# ProProject_Tautek_nRF5340_2024-01-15.net
KiCad netlist of a schematic drawn in EasyEDA Pro
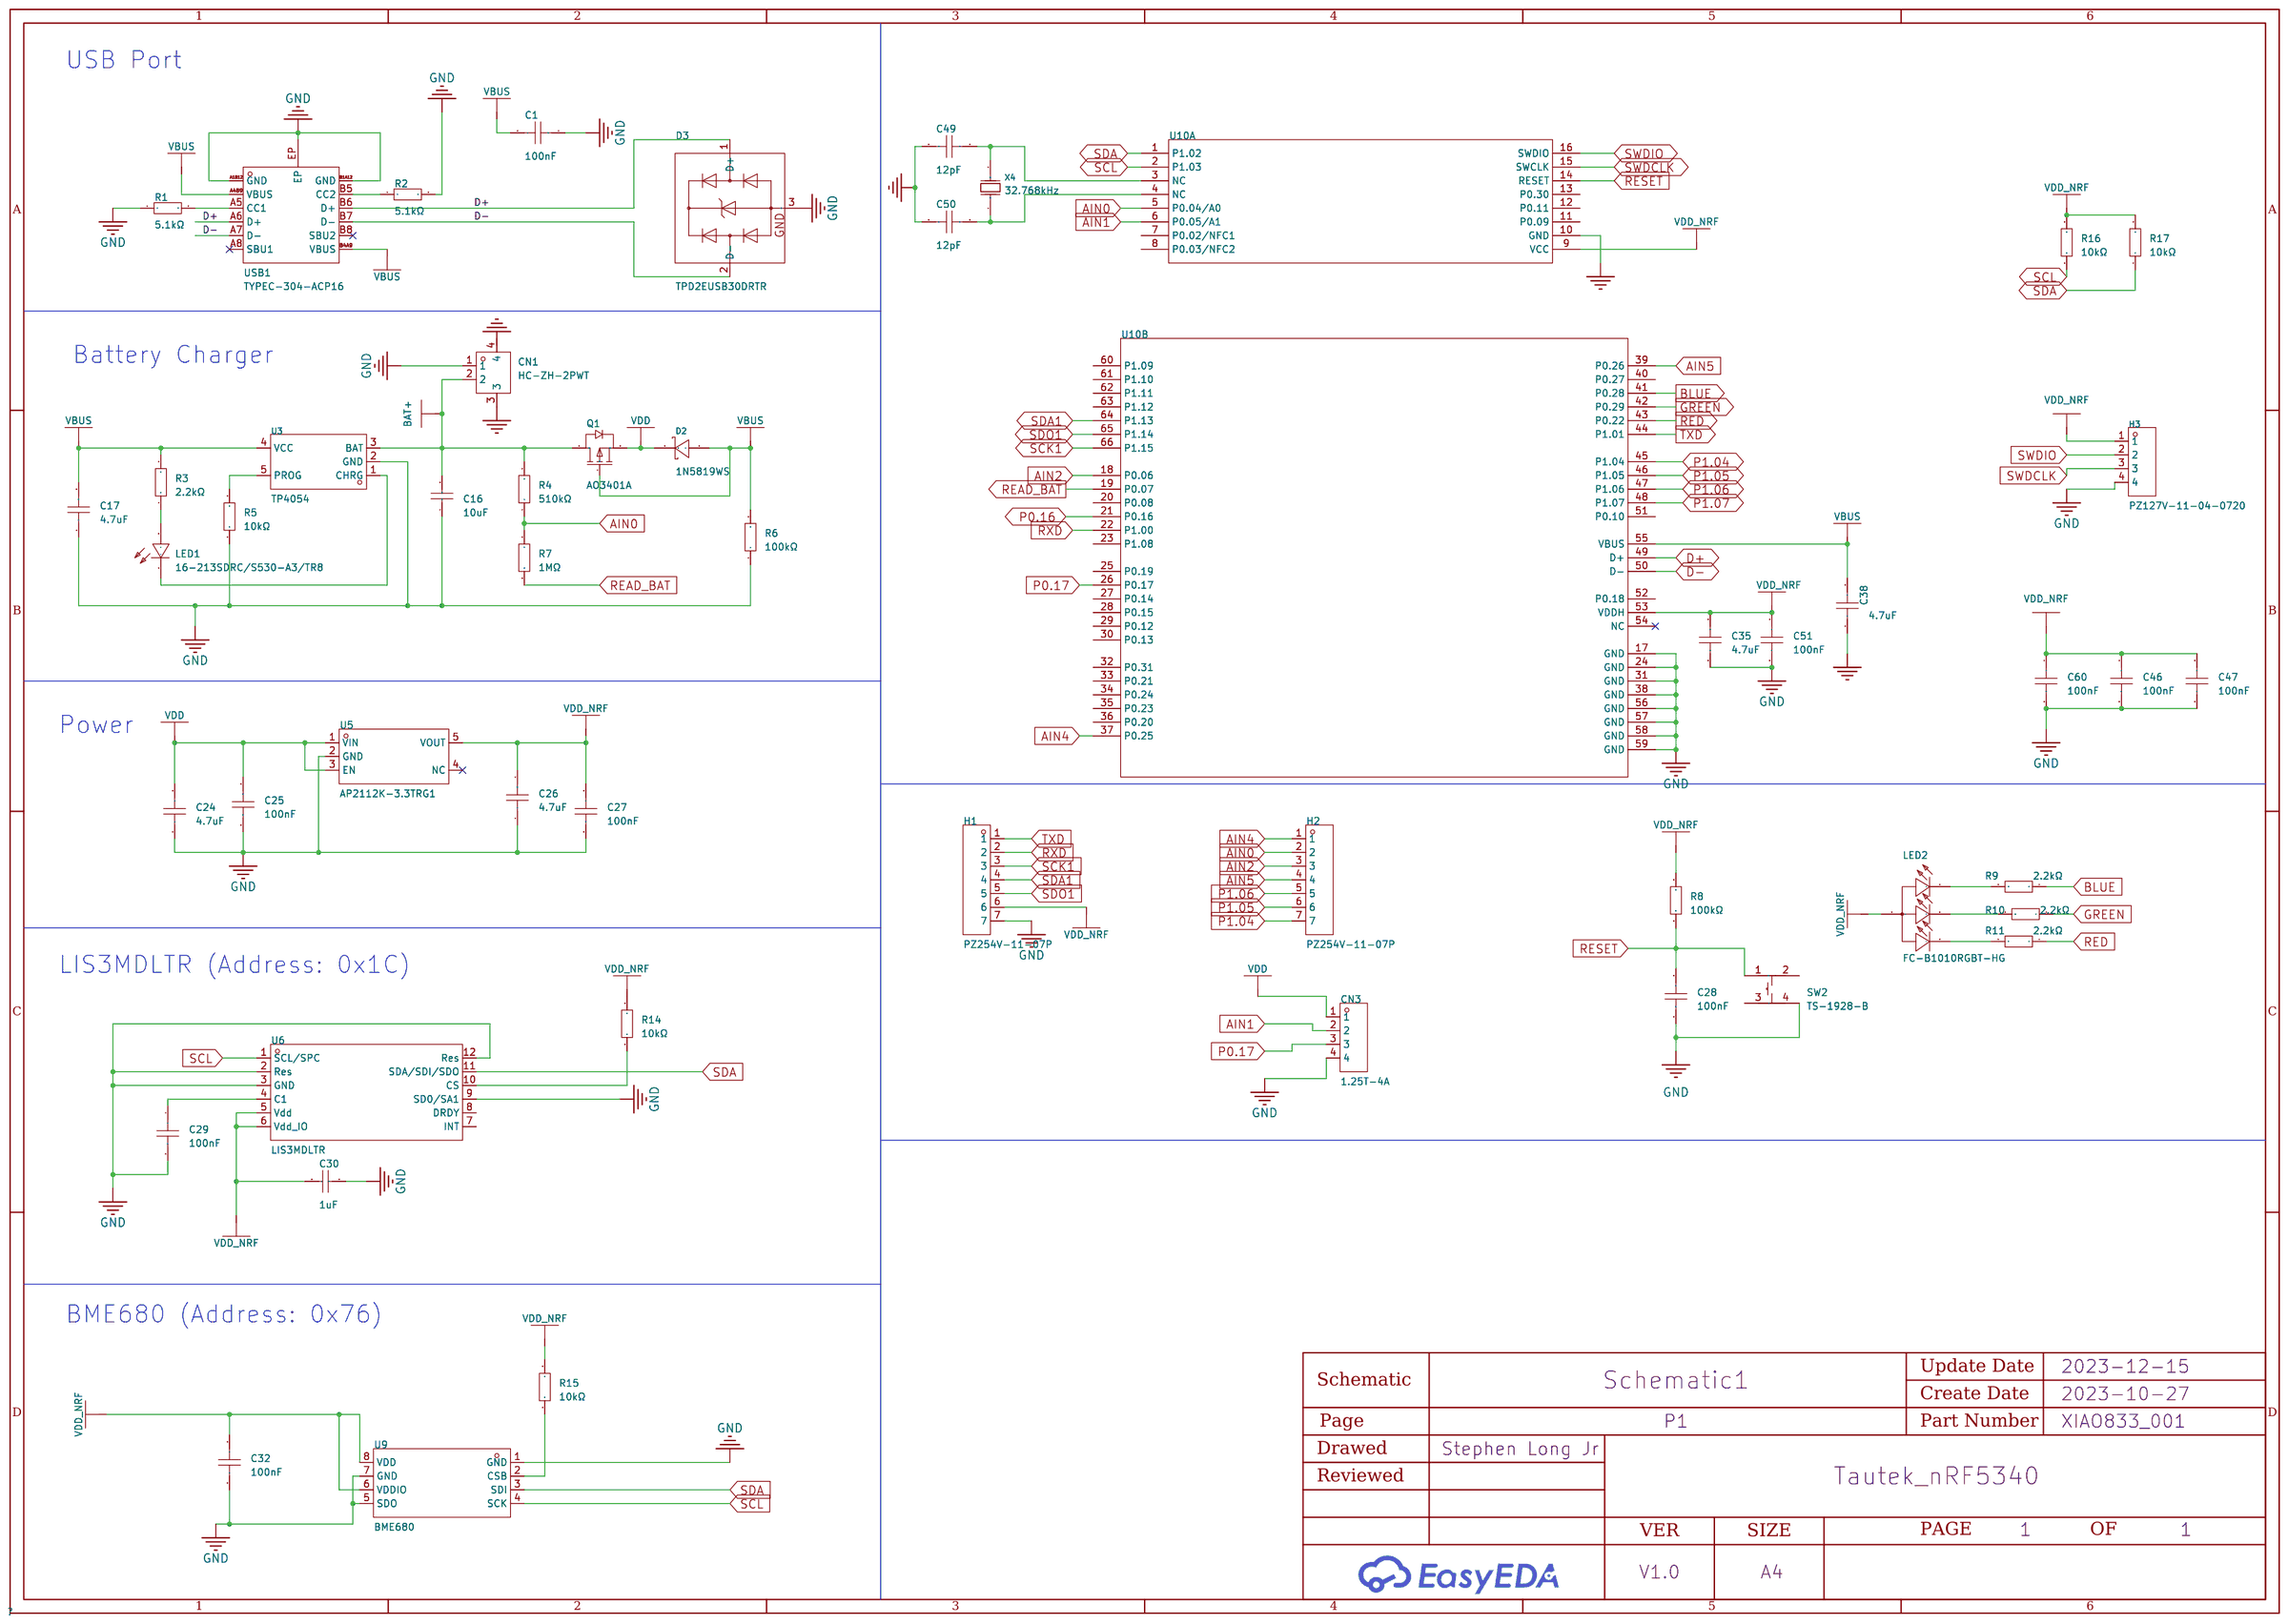
[diagram p0: schematic sheet]

(export (version "E")
  (design (tool "Eeschema 10.0.6"))
  (components
    (comp (ref "C1")
      (value "100nF")
      (footprint "easyedapro:C0201")
      (fields
        (field (name "Manufacturer Part") "CL03A104KQ3NNNC")
        (field (name "Manufacturer") "SAMSUNG(三星)")
      )
      (libsource (lib "easyedapro") (part "CL03A104KQ3NNNC"))
    )
    (comp (ref "C16")
      (value "10uF")
      (footprint "easyedapro:C0402")
      (fields
        (field (name "Manufacturer Part") "CL05A106MQ5NUNC")
        (field (name "Manufacturer") "SAMSUNG(三星)")
      )
      (libsource (lib "easyedapro") (part "CL05A106MQ5NUNC"))
    )
    (comp (ref "C17")
      (value "4.7uF")
      (footprint "easyedapro:C0201")
      (fields
        (field (name "Manufacturer Part") "GRM035R60J475ME15D")
        (field (name "Manufacturer") "muRata(村田)")
      )
      (libsource (lib "easyedapro") (part "GRM035R60J475ME15D"))
    )
    (comp (ref "C24")
      (value "4.7uF")
      (footprint "easyedapro:C0201")
      (fields
        (field (name "Manufacturer Part") "GRM035R60J475ME15D")
        (field (name "Manufacturer") "muRata(村田)")
      )
      (libsource (lib "easyedapro") (part "GRM035R60J475ME15D"))
    )
    (comp (ref "C25")
      (value "100nF")
      (footprint "easyedapro:C0201")
      (fields
        (field (name "Manufacturer Part") "CL03A104KQ3NNNC")
        (field (name "Manufacturer") "SAMSUNG(三星)")
      )
      (libsource (lib "easyedapro") (part "CL03A104KQ3NNNC"))
    )
    (comp (ref "C26")
      (value "4.7uF")
      (footprint "easyedapro:C0201")
      (fields
        (field (name "Manufacturer Part") "GRM035R60J475ME15D")
        (field (name "Manufacturer") "muRata(村田)")
      )
      (libsource (lib "easyedapro") (part "GRM035R60J475ME15D"))
    )
    (comp (ref "C27")
      (value "100nF")
      (footprint "easyedapro:C0201")
      (fields
        (field (name "Manufacturer Part") "CL03A104KQ3NNNC")
        (field (name "Manufacturer") "SAMSUNG(三星)")
      )
      (libsource (lib "easyedapro") (part "CL03A104KQ3NNNC"))
    )
    (comp (ref "C28")
      (value "100nF")
      (footprint "easyedapro:C0201")
      (fields
        (field (name "Manufacturer Part") "CL03A104KQ3NNNC")
        (field (name "Manufacturer") "SAMSUNG(三星)")
      )
      (libsource (lib "easyedapro") (part "CL03A104KQ3NNNC"))
    )
    (comp (ref "C29")
      (value "100nF")
      (footprint "easyedapro:C0201")
      (fields
        (field (name "Manufacturer Part") "CL03A104KQ3NNNC")
        (field (name "Manufacturer") "SAMSUNG(三星)")
      )
      (libsource (lib "easyedapro") (part "CL03A104KQ3NNNC"))
    )
    (comp (ref "C30")
      (value "1uF")
      (footprint "easyedapro:C0201")
      (fields
        (field (name "Manufacturer Part") "GRM033R60J105KEA2D")
        (field (name "Manufacturer") "muRata(村田)")
      )
      (libsource (lib "easyedapro") (part "GRM033R60J105KEA2D"))
    )
    (comp (ref "C32")
      (value "100nF")
      (footprint "easyedapro:C0201")
      (fields
        (field (name "Manufacturer Part") "CL03A104KQ3NNNC")
        (field (name "Manufacturer") "SAMSUNG(三星)")
      )
      (libsource (lib "easyedapro") (part "CL03A104KQ3NNNC"))
    )
    (comp (ref "C35")
      (value "4.7uF")
      (footprint "easyedapro:C0201")
      (fields
        (field (name "Manufacturer Part") "GRM035R60J475ME15D")
        (field (name "Manufacturer") "muRata(村田)")
      )
      (libsource (lib "easyedapro") (part "GRM035R60J475ME15D"))
    )
    (comp (ref "C38")
      (value "4.7uF")
      (footprint "easyedapro:C0201")
      (fields
        (field (name "Manufacturer Part") "GRM035R60J475ME15D")
        (field (name "Manufacturer") "muRata(村田)")
      )
      (libsource (lib "easyedapro") (part "GRM035R60J475ME15D"))
    )
    (comp (ref "C46")
      (value "100nF")
      (footprint "easyedapro:C0201")
      (fields
        (field (name "Manufacturer Part") "CL03A104KQ3NNNC")
        (field (name "Manufacturer") "SAMSUNG(三星)")
      )
      (libsource (lib "easyedapro") (part "CL03A104KQ3NNNC"))
    )
    (comp (ref "C47")
      (value "100nF")
      (footprint "easyedapro:C0201")
      (fields
        (field (name "Manufacturer Part") "CL03A104KQ3NNNC")
        (field (name "Manufacturer") "SAMSUNG(三星)")
      )
      (libsource (lib "easyedapro") (part "CL03A104KQ3NNNC"))
    )
    (comp (ref "C49")
      (value "12pF")
      (footprint "easyedapro:C0201")
      (fields
        (field (name "Manufacturer Part") "GRM0335C1H120FA01D")
        (field (name "Manufacturer") "muRata(村田)")
      )
      (libsource (lib "easyedapro") (part "GRM0335C1H120FA01D"))
    )
    (comp (ref "C50")
      (value "12pF")
      (footprint "easyedapro:C0201")
      (fields
        (field (name "Manufacturer Part") "GRM0335C1H120FA01D")
        (field (name "Manufacturer") "muRata(村田)")
      )
      (libsource (lib "easyedapro") (part "GRM0335C1H120FA01D"))
    )
    (comp (ref "C51")
      (value "100nF")
      (footprint "easyedapro:C0201")
      (fields
        (field (name "Manufacturer Part") "CL03A104KQ3NNNC")
        (field (name "Manufacturer") "SAMSUNG(三星)")
      )
      (libsource (lib "easyedapro") (part "CL03A104KQ3NNNC"))
    )
    (comp (ref "C60")
      (value "100nF")
      (footprint "easyedapro:C0201")
      (fields
        (field (name "Manufacturer Part") "CL03A104KQ3NNNC")
        (field (name "Manufacturer") "SAMSUNG(三星)")
      )
      (libsource (lib "easyedapro") (part "CL03A104KQ3NNNC"))
    )
    (comp (ref "CN1")
      (value "HC-ZH-2PWT")
      (footprint "easyedapro:CONN-SMD_2P-P1.50_HCTL_HC-ZH-2PWT")
      (fields (field (name "Manufacturer") "HCTL(华灿天禄)"))
      (libsource (lib "easyedapro") (part "HC-ZH-2PWT"))
    )
    (comp (ref "CN3")
      (value "1.25T-4A")
      (footprint "easyedapro:CONN-TH_11.25T-4A")
      (fields (field (name "Manufacturer") "CAX(创都)"))
      (libsource (lib "easyedapro") (part "1.25T-4A_C722638"))
    )
    (comp (ref "D2")
      (value "1N5819WS")
      (footprint "easyedapro:SOD-323_L1.8-W1.3-LS2.5-RD")
      (description "Reverse Voltage (Vr):40V Average Rectified Current (Io):1A Forward Voltage (Vf@If):600mV@1A")
      (fields (field (name "Manufacturer") "Hottech(合科泰)"))
      (libsource (lib "easyedapro") (part "1N5819WS"))
    )
    (comp (ref "D3")
      (value "TPD2EUSB30DRTR")
      (footprint "easyedapro:SOT-9X3-3_L1.0-W0.8-P0.35-LS1.0-BR")
      (fields (field (name "Manufacturer") "TI(德州仪器)"))
      (libsource (lib "easyedapro") (part "TPD2EUSB30DRTR"))
    )
    (comp (ref "H1")
      (value "PZ254V-11-07P")
      (footprint "easyedapro:HDR-TH_7P-P2.54-V-M")
      (fields (field (name "Manufacturer") "XFCN(兴飞)"))
      (libsource (lib "easyedapro") (part "PZ254V-11-07P"))
    )
    (comp (ref "H2")
      (value "PZ254V-11-07P")
      (footprint "easyedapro:HDR-TH_7P-P2.54-V-M")
      (fields (field (name "Manufacturer") "XFCN(兴飞)"))
      (libsource (lib "easyedapro") (part "PZ254V-11-07P"))
    )
    (comp (ref "H3")
      (value "PZ127V-11-04-0720")
      (footprint "easyedapro:HDR-TH_4P-P1.27-V-M")
      (fields (field (name "Manufacturer") "XFCN(兴飞)"))
      (libsource (lib "easyedapro") (part "PZ127V-11-04-0720"))
    )
    (comp (ref "LED1")
      (value "16-213SDRC/S530-A3/TR8")
      (footprint "easyedapro:LED0402-RD")
      (fields (field (name "Manufacturer") "EVERLIGHT(亿光)"))
      (libsource (lib "easyedapro") (part "16-213/SDRC/S530-A3/TR8"))
    )
    (comp (ref "LED2")
      (value "FC-B1010RGBT-HG")
      (footprint "easyedapro:LED-ARRAY-SMD_4P-L1.0-W1.0-TR-RD")
      (description "Emitted Color:RGB")
      (fields (field (name "Manufacturer") "国星光电"))
      (libsource (lib "easyedapro") (part "FC-B1010RGBT-HG"))
    )
    (comp (ref "Q1")
      (value "AO3401A")
      (footprint "easyedapro:SOT-23_L2.9-W1.3-P1.90-LS2.4-BR")
      (fields (field (name "Manufacturer") "UMW(广东友台半导体)"))
      (libsource (lib "easyedapro") (part "AO3401A_C347476"))
    )
    (comp (ref "R1")
      (value "5.1kΩ")
      (footprint "easyedapro:R0201")
      (fields (field (name "Manufacturer Part") "RC0201FR-075K1L") (field (name "Manufacturer") "YAGEO(国巨)"))
      (libsource (lib "easyedapro") (part "RC0201FR-075K1L"))
    )
    (comp (ref "R2")
      (value "5.1kΩ")
      (footprint "easyedapro:R0201")
      (fields (field (name "Manufacturer Part") "RC0201FR-075K1L") (field (name "Manufacturer") "YAGEO(国巨)"))
      (libsource (lib "easyedapro") (part "RC0201FR-075K1L"))
    )
    (comp (ref "R3")
      (value "2.2kΩ")
      (footprint "easyedapro:R0201")
      (fields (field (name "Manufacturer Part") "RC0201FR-072K2L") (field (name "Manufacturer") "YAGEO(国巨)"))
      (libsource (lib "easyedapro") (part "RC0201FR-072K2L"))
    )
    (comp (ref "R4")
      (value "510kΩ")
      (footprint "easyedapro:R0201")
      (fields (field (name "Manufacturer Part") "RC0201FR-07510KL") (field (name "Manufacturer") "YAGEO(国巨)"))
      (libsource (lib "easyedapro") (part "RC0201FR-07510KL"))
    )
    (comp (ref "R5")
      (value "10kΩ")
      (footprint "easyedapro:R0201")
      (fields (field (name "Manufacturer Part") "RC0201FR-0710KL") (field (name "Manufacturer") "YAGEO(国巨)"))
      (libsource (lib "easyedapro") (part "RC0201FR-0710KL"))
    )
    (comp (ref "R6")
      (value "100kΩ")
      (footprint "easyedapro:R0201")
      (fields (field (name "Manufacturer Part") "RC0201FR-07100KL") (field (name "Manufacturer") "YAGEO(国巨)"))
      (libsource (lib "easyedapro") (part "RC0201FR-07100KL"))
    )
    (comp (ref "R7")
      (value "1MΩ")
      (footprint "easyedapro:R0201")
      (fields (field (name "Manufacturer Part") "RC0201FR-071ML") (field (name "Manufacturer") "YAGEO(国巨)"))
      (libsource (lib "easyedapro") (part "RC0201FR-071ML"))
    )
    (comp (ref "R8")
      (value "100kΩ")
      (footprint "easyedapro:R0201")
      (fields (field (name "Manufacturer Part") "RC0201FR-07100KL") (field (name "Manufacturer") "YAGEO(国巨)"))
      (libsource (lib "easyedapro") (part "RC0201FR-07100KL"))
    )
    (comp (ref "R9")
      (value "2.2kΩ")
      (footprint "easyedapro:R0201")
      (fields (field (name "Manufacturer Part") "RC0201FR-072K2L") (field (name "Manufacturer") "YAGEO(国巨)"))
      (libsource (lib "easyedapro") (part "RC0201FR-072K2L"))
    )
    (comp (ref "R10")
      (value "2.2kΩ")
      (footprint "easyedapro:R0201")
      (fields (field (name "Manufacturer Part") "RC0201FR-072K2L") (field (name "Manufacturer") "YAGEO(国巨)"))
      (libsource (lib "easyedapro") (part "RC0201FR-072K2L"))
    )
    (comp (ref "R11")
      (value "2.2kΩ")
      (footprint "easyedapro:R0201")
      (fields (field (name "Manufacturer Part") "RC0201FR-072K2L") (field (name "Manufacturer") "YAGEO(国巨)"))
      (libsource (lib "easyedapro") (part "RC0201FR-072K2L"))
    )
    (comp (ref "R14")
      (value "10kΩ")
      (footprint "easyedapro:R0201")
      (fields (field (name "Manufacturer Part") "RC0201FR-0710KL") (field (name "Manufacturer") "YAGEO(国巨)"))
      (libsource (lib "easyedapro") (part "RC0201FR-0710KL"))
    )
    (comp (ref "R15")
      (value "10kΩ")
      (footprint "easyedapro:R0201")
      (fields (field (name "Manufacturer Part") "RC0201FR-0710KL") (field (name "Manufacturer") "YAGEO(国巨)"))
      (libsource (lib "easyedapro") (part "RC0201FR-0710KL"))
    )
    (comp (ref "R16")
      (value "10kΩ")
      (footprint "easyedapro:R0201")
      (fields (field (name "Manufacturer Part") "RC0201FR-0710KL") (field (name "Manufacturer") "YAGEO(国巨)"))
      (libsource (lib "easyedapro") (part "RC0201FR-0710KL"))
    )
    (comp (ref "R17")
      (value "10kΩ")
      (footprint "easyedapro:R0201")
      (fields (field (name "Manufacturer Part") "RC0201FR-0710KL") (field (name "Manufacturer") "YAGEO(国巨)"))
      (libsource (lib "easyedapro") (part "RC0201FR-0710KL"))
    )
    (comp (ref "SW2")
      (value "TS-1928-B")
      (footprint "easyedapro:KEY-SMD_4P-L2.8-W2.0-P1.20-LS3.0-TL")
      (fields (field (name "Manufacturer") "XKBConnectivity(中国星坤)"))
      (libsource (lib "easyedapro") (part "TS-1928-B"))
    )
    (comp (ref "U3")
      (value "TP4054")
      (footprint "easyedapro:TSOT-23-5_L2.9-W1.6-P0.95-LS2.8-BR")
      (fields (field (name "Manufacturer") "UMW(友台半导体)"))
      (libsource (lib "easyedapro") (part "TP4054_C668215"))
    )
    (comp (ref "U5")
      (value "AP2112K-3.3TRG1")
      (footprint "easyedapro:SOT-25-5_L2.9-W1.6-P0.95-LS2.8-BL")
      (fields (field (name "Manufacturer") "DIODES(美台)"))
      (libsource (lib "easyedapro") (part "AP2112K-3.3TRG1"))
    )
    (comp (ref "U6")
      (value "LIS3MDLTR")
      (footprint "easyedapro:LGA-12_L2.0-W2.0-P0.50-BL")
      (fields (field (name "Manufacturer") "ST(意法半导体)"))
      (libsource (lib "easyedapro") (part "LIS3MDLTR"))
    )
    (comp (ref "U9")
      (value "BME680")
      (footprint "easyedapro:LGA-8_L3.0-W3.0-P0.80-TR")
      (fields (field (name "Manufacturer") "Bosch(博世)"))
      (libsource (lib "easyedapro") (part "BME680"))
    )
    (comp (ref "U10") (value "~") (footprint "easyedapro:BT40") (libsource (lib "easyedapro") (part "BT40E")))
    (comp (ref "USB1")
      (value "TYPEC-304-ACP16")
      (footprint "easyedapro:USB-C-SMD_TYPE-C-16P-1")
      (fields (field (name "Manufacturer") "XUNPU(讯普)"))
      (libsource (lib "easyedapro") (part "TYPEC-304-ACP16"))
    )
    (comp (ref "X4")
      (value "32.768kHz")
      (footprint "easyedapro:CRYSTAL-SMD_L1.7-W1.1")
      (fields (field (name "Manufacturer Part") "X1A000121000500") (field (name "Manufacturer") "EPSON(爱普生)"))
      (libsource (lib "easyedapro") (part "X1A000121000500"))
    )
  )
  (nets
    (net (code "1") (name "AIN0") (class "Default")
      (node (ref "H2") (pin "2") (pinfunction "2_2") (pintype "input"))
      (node (ref "R4") (pin "1") (pinfunction "1_1") (pintype "input"))
      (node (ref "R7") (pin "1") (pinfunction "1_1") (pintype "input"))
      (node (ref "U10") (pin "5") (pinfunction "P0.04/A0_5") (pintype "input"))
    )
    (net (code "2") (name "AIN1") (class "Default")
      (node (ref "CN3") (pin "2") (pinfunction "2_2") (pintype "input"))
      (node (ref "U10") (pin "6") (pinfunction "P0.05/A1_6") (pintype "input"))
    )
    (net (code "3") (name "AIN2") (class "Default")
      (node (ref "H2") (pin "3") (pinfunction "3_3") (pintype "input"))
      (node (ref "U10") (pin "18") (pinfunction "P0.06_18") (pintype "input"))
    )
    (net (code "4") (name "AIN4") (class "Default")
      (node (ref "H2") (pin "1") (pinfunction "1_1") (pintype "input"))
      (node (ref "U10") (pin "37") (pinfunction "P0.25_37") (pintype "input"))
    )
    (net (code "5") (name "AIN5") (class "Default")
      (node (ref "H2") (pin "4") (pinfunction "4_4") (pintype "input"))
      (node (ref "U10") (pin "39") (pinfunction "P0.26_39") (pintype "input"))
    )
    (net (code "6") (name "BAT+") (class "Default")
      (node (ref "C16") (pin "2") (pinfunction "2_2") (pintype "input"))
      (node (ref "CN1") (pin "2") (pinfunction "2_2") (pintype "input"))
      (node (ref "Q1") (pin "3") (pinfunction "D_3") (pintype "input"))
      (node (ref "R4") (pin "2") (pinfunction "2_2") (pintype "input"))
      (node (ref "U3") (pin "3") (pinfunction "BAT_3") (pintype "input"))
    )
    (net (code "7") (name "BLUE") (class "Default")
      (node (ref "R9") (pin "1") (pinfunction "1_1") (pintype "input"))
      (node (ref "U10") (pin "41") (pinfunction "P0.28_41") (pintype "input"))
    )
    (net (code "8") (name "D+") (class "Default")
      (node (ref "D3") (pin "1") (pinfunction "D+_1") (pintype "input"))
      (node (ref "U10") (pin "49") (pinfunction "D+_49") (pintype "input"))
      (node (ref "USB1") (pin "A6") (pinfunction "D+_A6") (pintype "input"))
      (node (ref "USB1") (pin "B6") (pinfunction "D+_B6") (pintype "input"))
    )
    (net (code "9") (name "D-") (class "Default")
      (node (ref "D3") (pin "2") (pinfunction "D-_2") (pintype "input"))
      (node (ref "U10") (pin "50") (pinfunction "D-_50") (pintype "input"))
      (node (ref "USB1") (pin "A7") (pinfunction "D-_A7") (pintype "input"))
      (node (ref "USB1") (pin "B7") (pinfunction "D-_B7") (pintype "input"))
    )
    (net (code "10") (name "GND") (class "Default")
      (node (ref "C1") (pin "1") (pinfunction "1_1") (pintype "input"))
      (node (ref "C16") (pin "1") (pinfunction "1_1") (pintype "input"))
      (node (ref "C17") (pin "1") (pinfunction "1_1") (pintype "input"))
      (node (ref "C24") (pin "1") (pinfunction "1_1") (pintype "input"))
      (node (ref "C25") (pin "2") (pinfunction "2_2") (pintype "input"))
      (node (ref "C26") (pin "1") (pinfunction "1_1") (pintype "input"))
      (node (ref "C27") (pin "2") (pinfunction "2_2") (pintype "input"))
      (node (ref "C28") (pin "1") (pinfunction "1_1") (pintype "input"))
      (node (ref "C29") (pin "2") (pinfunction "2_2") (pintype "input"))
      (node (ref "C30") (pin "2") (pinfunction "2_2") (pintype "input"))
      (node (ref "C32") (pin "1") (pinfunction "1_1") (pintype "input"))
      (node (ref "C35") (pin "1") (pinfunction "1_1") (pintype "input"))
      (node (ref "C38") (pin "1") (pinfunction "1_1") (pintype "input"))
      (node (ref "C46") (pin "2") (pinfunction "2_2") (pintype "input"))
      (node (ref "C47") (pin "2") (pinfunction "2_2") (pintype "input"))
      (node (ref "C49") (pin "1") (pinfunction "1_1") (pintype "input"))
      (node (ref "C50") (pin "1") (pinfunction "1_1") (pintype "input"))
      (node (ref "C51") (pin "2") (pinfunction "2_2") (pintype "input"))
      (node (ref "C60") (pin "2") (pinfunction "2_2") (pintype "input"))
      (node (ref "CN1") (pin "1") (pinfunction "1_1") (pintype "input"))
      (node (ref "CN1") (pin "3") (pinfunction "3_3") (pintype "input"))
      (node (ref "CN3") (pin "4") (pinfunction "4_4") (pintype "input"))
      (node (ref "D3") (pin "3") (pinfunction "GND_3") (pintype "input"))
      (node (ref "H1") (pin "7") (pinfunction "7_7") (pintype "input"))
      (node (ref "H3") (pin "4") (pinfunction "4_4") (pintype "input"))
      (node (ref "R1") (pin "1") (pinfunction "1_1") (pintype "input"))
      (node (ref "R2") (pin "2") (pinfunction "2_2") (pintype "input"))
      (node (ref "R5") (pin "1") (pinfunction "1_1") (pintype "input"))
      (node (ref "R6") (pin "1") (pinfunction "1_1") (pintype "input"))
      (node (ref "SW2") (pin "4") (pinfunction "4_4") (pintype "input"))
      (node (ref "U10") (pin "10") (pinfunction "GND_10") (pintype "input"))
      (node (ref "U10") (pin "17") (pinfunction "GND_17") (pintype "input"))
      (node (ref "U10") (pin "24") (pinfunction "GND_24") (pintype "input"))
      (node (ref "U10") (pin "31") (pinfunction "GND_31") (pintype "input"))
      (node (ref "U10") (pin "38") (pinfunction "GND_38") (pintype "input"))
      (node (ref "U10") (pin "56") (pinfunction "GND_56") (pintype "input"))
      (node (ref "U10") (pin "57") (pinfunction "GND_57") (pintype "input"))
      (node (ref "U10") (pin "58") (pinfunction "GND_58") (pintype "input"))
      (node (ref "U10") (pin "59") (pinfunction "GND_59") (pintype "input"))
      (node (ref "U3") (pin "2") (pinfunction "GND_2") (pintype "input"))
      (node (ref "U5") (pin "2") (pinfunction "GND_2") (pintype "input"))
      (node (ref "U6") (pin "12") (pinfunction "Res_12") (pintype "input"))
      (node (ref "U6") (pin "2") (pinfunction "Res_2") (pintype "input"))
      (node (ref "U6") (pin "3") (pinfunction "GND_3") (pintype "input"))
      (node (ref "U6") (pin "9") (pinfunction "SD0/SA1_9") (pintype "input"))
      (node (ref "U9") (pin "1") (pinfunction "GND_1") (pintype "input"))
      (node (ref "U9") (pin "5") (pinfunction "SDO_5") (pintype "input"))
      (node (ref "U9") (pin "7") (pinfunction "GND_7") (pintype "input"))
      (node (ref "USB1") (pin "A1B12") (pinfunction "GND_A1B12") (pintype "input"))
      (node (ref "USB1") (pin "B1A12") (pinfunction "GND_B1A12") (pintype "input"))
      (node (ref "USB1") (pin "EP") (pinfunction "EP_EP") (pintype "input"))
    )
    (net (code "11") (name "GREEN") (class "Default")
      (node (ref "R10") (pin "1") (pinfunction "1_1") (pintype "input"))
      (node (ref "U10") (pin "42") (pinfunction "P0.29_42") (pintype "input"))
    )
    (net (code "12") (name "Net-(LED1-+)") (class "Default")
      (node (ref "LED1") (pin "2") (pinfunction "+_2") (pintype "input"))
      (node (ref "R3") (pin "1") (pinfunction "1_1") (pintype "input"))
    )
    (net (code "13") (name "Net-(LED1--)") (class "Default")
      (node (ref "LED1") (pin "1") (pinfunction "-_1") (pintype "input"))
      (node (ref "U3") (pin "1") (pinfunction "CHRG_1") (pintype "input"))
    )
    (net (code "14") (name "Net-(LED2---Pad2)") (class "Default")
      (node (ref "LED2") (pin "2") (pinfunction "-_2") (pintype "input"))
      (node (ref "R11") (pin "2") (pinfunction "2_2") (pintype "input"))
    )
    (net (code "15") (name "Net-(LED2---Pad3)") (class "Default")
      (node (ref "LED2") (pin "3") (pinfunction "-_3") (pintype "input"))
      (node (ref "R10") (pin "2") (pinfunction "2_2") (pintype "input"))
    )
    (net (code "16") (name "Net-(LED2---Pad4)") (class "Default")
      (node (ref "LED2") (pin "4") (pinfunction "-_4") (pintype "input"))
      (node (ref "R9") (pin "2") (pinfunction "2_2") (pintype "input"))
    )
    (net (code "17") (name "Net-(U3-PROG)") (class "Default")
      (node (ref "R5") (pin "2") (pinfunction "2_2") (pintype "input"))
      (node (ref "U3") (pin "5") (pinfunction "PROG_5") (pintype "input"))
    )
    (net (code "18") (name "Net-(U6-C1)") (class "Default")
      (node (ref "C29") (pin "1") (pinfunction "1_1") (pintype "input"))
      (node (ref "U6") (pin "4") (pinfunction "C1_4") (pintype "input"))
    )
    (net (code "19") (name "Net-(U6-CS)") (class "Default")
      (node (ref "R14") (pin "1") (pinfunction "1_1") (pintype "input"))
      (node (ref "U6") (pin "10") (pinfunction "CS_10") (pintype "input"))
    )
    (net (code "20") (name "Net-(U9-CSB)") (class "Default")
      (node (ref "R15") (pin "1") (pinfunction "1_1") (pintype "input"))
      (node (ref "U9") (pin "2") (pinfunction "CSB_2") (pintype "input"))
    )
    (net (code "21") (name "Net-(USB1-CC1)") (class "Default")
      (node (ref "R1") (pin "2") (pinfunction "2_2") (pintype "input"))
      (node (ref "USB1") (pin "A5") (pinfunction "CC1_A5") (pintype "input"))
    )
    (net (code "22") (name "Net-(USB1-CC2)") (class "Default")
      (node (ref "R2") (pin "1") (pinfunction "1_1") (pintype "input"))
      (node (ref "USB1") (pin "B5") (pinfunction "CC2_B5") (pintype "input"))
    )
    (net (code "23") (name "Net-(X4-OSC1)") (class "Default")
      (node (ref "C50") (pin "2") (pinfunction "2_2") (pintype "input"))
      (node (ref "U10") (pin "4") (pinfunction "NC_4") (pintype "input"))
      (node (ref "X4") (pin "1") (pinfunction "OSC1_1") (pintype "input"))
    )
    (net (code "24") (name "Net-(X4-OSC2)") (class "Default")
      (node (ref "C49") (pin "2") (pinfunction "2_2") (pintype "input"))
      (node (ref "U10") (pin "3") (pinfunction "NC_3") (pintype "input"))
      (node (ref "X4") (pin "2") (pinfunction "OSC2_2") (pintype "input"))
    )
    (net (code "25") (name "P0.16") (class "Default")
      (node (ref "U10") (pin "21") (pinfunction "P0.16_21") (pintype "input"))
    )
    (net (code "26") (name "P0.17") (class "Default")
      (node (ref "CN3") (pin "3") (pinfunction "3_3") (pintype "input"))
      (node (ref "U10") (pin "26") (pinfunction "P0.17_26") (pintype "input"))
    )
    (net (code "27") (name "P1.04") (class "Default")
      (node (ref "H2") (pin "7") (pinfunction "7_7") (pintype "input"))
      (node (ref "U10") (pin "45") (pinfunction "P1.04_45") (pintype "input"))
    )
    (net (code "28") (name "P1.05") (class "Default")
      (node (ref "H2") (pin "6") (pinfunction "6_6") (pintype "input"))
      (node (ref "U10") (pin "46") (pinfunction "P1.05_46") (pintype "input"))
    )
    (net (code "29") (name "P1.06") (class "Default")
      (node (ref "H2") (pin "5") (pinfunction "5_5") (pintype "input"))
      (node (ref "U10") (pin "47") (pinfunction "P1.06_47") (pintype "input"))
    )
    (net (code "30") (name "P1.07") (class "Default")
      (node (ref "U10") (pin "48") (pinfunction "P1.07_48") (pintype "input"))
    )
    (net (code "31") (name "READ_BAT") (class "Default")
      (node (ref "R7") (pin "2") (pinfunction "2_2") (pintype "input"))
      (node (ref "U10") (pin "19") (pinfunction "P0.07_19") (pintype "input"))
    )
    (net (code "32") (name "RED") (class "Default")
      (node (ref "R11") (pin "1") (pinfunction "1_1") (pintype "input"))
      (node (ref "U10") (pin "43") (pinfunction "P0.22_43") (pintype "input"))
    )
    (net (code "33") (name "RESET") (class "Default")
      (node (ref "C28") (pin "2") (pinfunction "2_2") (pintype "input"))
      (node (ref "R8") (pin "1") (pinfunction "1_1") (pintype "input"))
      (node (ref "SW2") (pin "1") (pinfunction "1_1") (pintype "input"))
      (node (ref "U10") (pin "14") (pinfunction "RESET_14") (pintype "input"))
    )
    (net (code "34") (name "RXD") (class "Default")
      (node (ref "H1") (pin "2") (pinfunction "2_2") (pintype "input"))
      (node (ref "U10") (pin "22") (pinfunction "P1.00_22") (pintype "input"))
    )
    (net (code "35") (name "SCK1") (class "Default")
      (node (ref "H1") (pin "3") (pinfunction "3_3") (pintype "input"))
      (node (ref "U10") (pin "66") (pinfunction "P1.15_66") (pintype "input"))
    )
    (net (code "36") (name "SCL") (class "Default")
      (node (ref "R16") (pin "1") (pinfunction "1_1") (pintype "input"))
      (node (ref "U10") (pin "2") (pinfunction "P1.03_2") (pintype "input"))
      (node (ref "U6") (pin "1") (pinfunction "SCL/SPC_1") (pintype "input"))
      (node (ref "U9") (pin "4") (pinfunction "SCK_4") (pintype "input"))
    )
    (net (code "37") (name "SDA") (class "Default")
      (node (ref "R17") (pin "1") (pinfunction "1_1") (pintype "input"))
      (node (ref "U10") (pin "1") (pinfunction "P1.02_1") (pintype "input"))
      (node (ref "U6") (pin "11") (pinfunction "SDA/SDI/SDO_11") (pintype "input"))
      (node (ref "U9") (pin "3") (pinfunction "SDI_3") (pintype "input"))
    )
    (net (code "38") (name "SDA1") (class "Default")
      (node (ref "H1") (pin "4") (pinfunction "4_4") (pintype "input"))
      (node (ref "U10") (pin "64") (pinfunction "P1.13_64") (pintype "input"))
    )
    (net (code "39") (name "SDO1") (class "Default")
      (node (ref "H1") (pin "5") (pinfunction "5_5") (pintype "input"))
      (node (ref "U10") (pin "65") (pinfunction "P1.14_65") (pintype "input"))
    )
    (net (code "40") (name "SWDCLK") (class "Default")
      (node (ref "H3") (pin "3") (pinfunction "3_3") (pintype "input"))
      (node (ref "U10") (pin "15") (pinfunction "SWCLK_15") (pintype "input"))
    )
    (net (code "41") (name "SWDIO") (class "Default")
      (node (ref "H3") (pin "2") (pinfunction "2_2") (pintype "input"))
      (node (ref "U10") (pin "16") (pinfunction "SWDIO_16") (pintype "input"))
    )
    (net (code "42") (name "TXD") (class "Default")
      (node (ref "H1") (pin "1") (pinfunction "1_1") (pintype "input"))
      (node (ref "U10") (pin "44") (pinfunction "P1.01_44") (pintype "input"))
    )
    (net (code "43") (name "VBUS") (class "Default")
      (node (ref "C1") (pin "2") (pinfunction "2_2") (pintype "input"))
      (node (ref "C17") (pin "2") (pinfunction "2_2") (pintype "input"))
      (node (ref "C38") (pin "2") (pinfunction "2_2") (pintype "input"))
      (node (ref "D2") (pin "2") (pinfunction "A_2") (pintype "input"))
      (node (ref "Q1") (pin "1") (pinfunction "G_1") (pintype "input"))
      (node (ref "R3") (pin "2") (pinfunction "2_2") (pintype "input"))
      (node (ref "R6") (pin "2") (pinfunction "2_2") (pintype "input"))
      (node (ref "U10") (pin "55") (pinfunction "VBUS_55") (pintype "input"))
      (node (ref "U3") (pin "4") (pinfunction "VCC_4") (pintype "input"))
      (node (ref "USB1") (pin "A4B9") (pinfunction "VBUS_A4B9") (pintype "input"))
      (node (ref "USB1") (pin "B4A9") (pinfunction "VBUS_B4A9") (pintype "input"))
    )
    (net (code "44") (name "VDD") (class "Default")
      (node (ref "C24") (pin "2") (pinfunction "2_2") (pintype "input"))
      (node (ref "C25") (pin "1") (pinfunction "1_1") (pintype "input"))
      (node (ref "CN3") (pin "1") (pinfunction "1_1") (pintype "input"))
      (node (ref "D2") (pin "1") (pinfunction "K_1") (pintype "input"))
      (node (ref "Q1") (pin "2") (pinfunction "S_2") (pintype "input"))
      (node (ref "U5") (pin "1") (pinfunction "VIN_1") (pintype "input"))
      (node (ref "U5") (pin "3") (pinfunction "EN_3") (pintype "input"))
    )
    (net (code "45") (name "VDD_NRF") (class "Default")
      (node (ref "C26") (pin "2") (pinfunction "2_2") (pintype "input"))
      (node (ref "C27") (pin "1") (pinfunction "1_1") (pintype "input"))
      (node (ref "C30") (pin "1") (pinfunction "1_1") (pintype "input"))
      (node (ref "C32") (pin "2") (pinfunction "2_2") (pintype "input"))
      (node (ref "C35") (pin "2") (pinfunction "2_2") (pintype "input"))
      (node (ref "C46") (pin "1") (pinfunction "1_1") (pintype "input"))
      (node (ref "C47") (pin "1") (pinfunction "1_1") (pintype "input"))
      (node (ref "C51") (pin "1") (pinfunction "1_1") (pintype "input"))
      (node (ref "C60") (pin "1") (pinfunction "1_1") (pintype "input"))
      (node (ref "H1") (pin "6") (pinfunction "6_6") (pintype "input"))
      (node (ref "H3") (pin "1") (pinfunction "1_1") (pintype "input"))
      (node (ref "LED2") (pin "1") (pinfunction "+_1") (pintype "input"))
      (node (ref "R14") (pin "2") (pinfunction "2_2") (pintype "input"))
      (node (ref "R15") (pin "2") (pinfunction "2_2") (pintype "input"))
      (node (ref "R16") (pin "2") (pinfunction "2_2") (pintype "input"))
      (node (ref "R17") (pin "2") (pinfunction "2_2") (pintype "input"))
      (node (ref "R8") (pin "2") (pinfunction "2_2") (pintype "input"))
      (node (ref "U10") (pin "53") (pinfunction "VDDH_53") (pintype "input"))
      (node (ref "U10") (pin "9") (pinfunction "VCC_9") (pintype "input"))
      (node (ref "U5") (pin "5") (pinfunction "VOUT_5") (pintype "input"))
      (node (ref "U6") (pin "5") (pinfunction "Vdd_5") (pintype "input"))
      (node (ref "U6") (pin "6") (pinfunction "Vdd_IO_6") (pintype "input"))
      (node (ref "U9") (pin "6") (pinfunction "VDDIO_6") (pintype "input"))
      (node (ref "U9") (pin "8") (pinfunction "VDD_8") (pintype "input"))
    )
    (net (code "46") (name "unconnected-(CN1-Pad4)") (class "Default")
      (node (ref "CN1") (pin "4") (pinfunction "4_4") (pintype "input"))
    )
    (net (code "47") (name "unconnected-(SW2-Pad2)") (class "Default")
      (node (ref "SW2") (pin "2") (pinfunction "2_2") (pintype "input"))
    )
    (net (code "48") (name "unconnected-(SW2-Pad3)") (class "Default")
      (node (ref "SW2") (pin "3") (pinfunction "3_3") (pintype "input"))
    )
    (net (code "49") (name "unconnected-(U5-NC-Pad4)") (class "Default")
      (node (ref "U5") (pin "4") (pinfunction "NC_4") (pintype "input+no_connect"))
    )
    (net (code "50") (name "unconnected-(U6-DRDY-Pad8)") (class "Default")
      (node (ref "U6") (pin "8") (pinfunction "DRDY_8") (pintype "input"))
    )
    (net (code "51") (name "unconnected-(U6-INT-Pad7)") (class "Default")
      (node (ref "U6") (pin "7") (pinfunction "INT_7") (pintype "input"))
    )
    (net (code "52") (name "unconnected-(U10A-P0.02{slash}NFC1-Pad7)") (class "Default")
      (node (ref "U10") (pin "7") (pinfunction "P0.02/NFC1_7") (pintype "input"))
    )
    (net (code "53") (name "unconnected-(U10A-P0.03{slash}NFC2-Pad8)") (class "Default")
      (node (ref "U10") (pin "8") (pinfunction "P0.03/NFC2_8") (pintype "input"))
    )
    (net (code "54") (name "unconnected-(U10A-P0.09-Pad11)") (class "Default")
      (node (ref "U10") (pin "11") (pinfunction "P0.09_11") (pintype "input"))
    )
    (net (code "55") (name "unconnected-(U10A-P0.11-Pad12)") (class "Default")
      (node (ref "U10") (pin "12") (pinfunction "P0.11_12") (pintype "input"))
    )
    (net (code "56") (name "unconnected-(U10A-P0.30-Pad13)") (class "Default")
      (node (ref "U10") (pin "13") (pinfunction "P0.30_13") (pintype "input"))
    )
    (net (code "57") (name "unconnected-(U10B-NC-Pad54)") (class "Default")
      (node (ref "U10") (pin "54") (pinfunction "NC_54") (pintype "input+no_connect"))
    )
    (net (code "58") (name "unconnected-(U10B-P0.08-Pad20)") (class "Default")
      (node (ref "U10") (pin "20") (pinfunction "P0.08_20") (pintype "input"))
    )
    (net (code "59") (name "unconnected-(U10B-P0.10-Pad51)") (class "Default")
      (node (ref "U10") (pin "51") (pinfunction "P0.10_51") (pintype "input"))
    )
    (net (code "60") (name "unconnected-(U10B-P0.12-Pad29)") (class "Default")
      (node (ref "U10") (pin "29") (pinfunction "P0.12_29") (pintype "input"))
    )
    (net (code "61") (name "unconnected-(U10B-P0.13-Pad30)") (class "Default")
      (node (ref "U10") (pin "30") (pinfunction "P0.13_30") (pintype "input"))
    )
    (net (code "62") (name "unconnected-(U10B-P0.14-Pad27)") (class "Default")
      (node (ref "U10") (pin "27") (pinfunction "P0.14_27") (pintype "input"))
    )
    (net (code "63") (name "unconnected-(U10B-P0.15-Pad28)") (class "Default")
      (node (ref "U10") (pin "28") (pinfunction "P0.15_28") (pintype "input"))
    )
    (net (code "64") (name "unconnected-(U10B-P0.18-Pad52)") (class "Default")
      (node (ref "U10") (pin "52") (pinfunction "P0.18_52") (pintype "input"))
    )
    (net (code "65") (name "unconnected-(U10B-P0.19-Pad25)") (class "Default")
      (node (ref "U10") (pin "25") (pinfunction "P0.19_25") (pintype "input"))
    )
    (net (code "66") (name "unconnected-(U10B-P0.20-Pad36)") (class "Default")
      (node (ref "U10") (pin "36") (pinfunction "P0.20_36") (pintype "input"))
    )
    (net (code "67") (name "unconnected-(U10B-P0.21-Pad33)") (class "Default")
      (node (ref "U10") (pin "33") (pinfunction "P0.21_33") (pintype "input"))
    )
    (net (code "68") (name "unconnected-(U10B-P0.23-Pad35)") (class "Default")
      (node (ref "U10") (pin "35") (pinfunction "P0.23_35") (pintype "input"))
    )
    (net (code "69") (name "unconnected-(U10B-P0.24-Pad34)") (class "Default")
      (node (ref "U10") (pin "34") (pinfunction "P0.24_34") (pintype "input"))
    )
    (net (code "70") (name "unconnected-(U10B-P0.27-Pad40)") (class "Default")
      (node (ref "U10") (pin "40") (pinfunction "P0.27_40") (pintype "input"))
    )
    (net (code "71") (name "unconnected-(U10B-P0.31-Pad32)") (class "Default")
      (node (ref "U10") (pin "32") (pinfunction "P0.31_32") (pintype "input"))
    )
    (net (code "72") (name "unconnected-(U10B-P1.08-Pad23)") (class "Default")
      (node (ref "U10") (pin "23") (pinfunction "P1.08_23") (pintype "input"))
    )
    (net (code "73") (name "unconnected-(U10B-P1.09-Pad60)") (class "Default")
      (node (ref "U10") (pin "60") (pinfunction "P1.09_60") (pintype "input"))
    )
    (net (code "74") (name "unconnected-(U10B-P1.10-Pad61)") (class "Default")
      (node (ref "U10") (pin "61") (pinfunction "P1.10_61") (pintype "input"))
    )
    (net (code "75") (name "unconnected-(U10B-P1.11-Pad62)") (class "Default")
      (node (ref "U10") (pin "62") (pinfunction "P1.11_62") (pintype "input"))
    )
    (net (code "76") (name "unconnected-(U10B-P1.12-Pad63)") (class "Default")
      (node (ref "U10") (pin "63") (pinfunction "P1.12_63") (pintype "input"))
    )
    (net (code "77") (name "unconnected-(USB1-SBU1-PadA8)") (class "Default")
      (node (ref "USB1") (pin "A8") (pinfunction "SBU1_A8") (pintype "input+no_connect"))
    )
    (net (code "78") (name "unconnected-(USB1-SBU2-PadB8)") (class "Default")
      (node (ref "USB1") (pin "B8") (pinfunction "SBU2_B8") (pintype "input+no_connect"))
    )
  )
)
